# TCAN1146_PWR_MGMT.net
KiCad netlist of a schematic drawn in Altium Designer
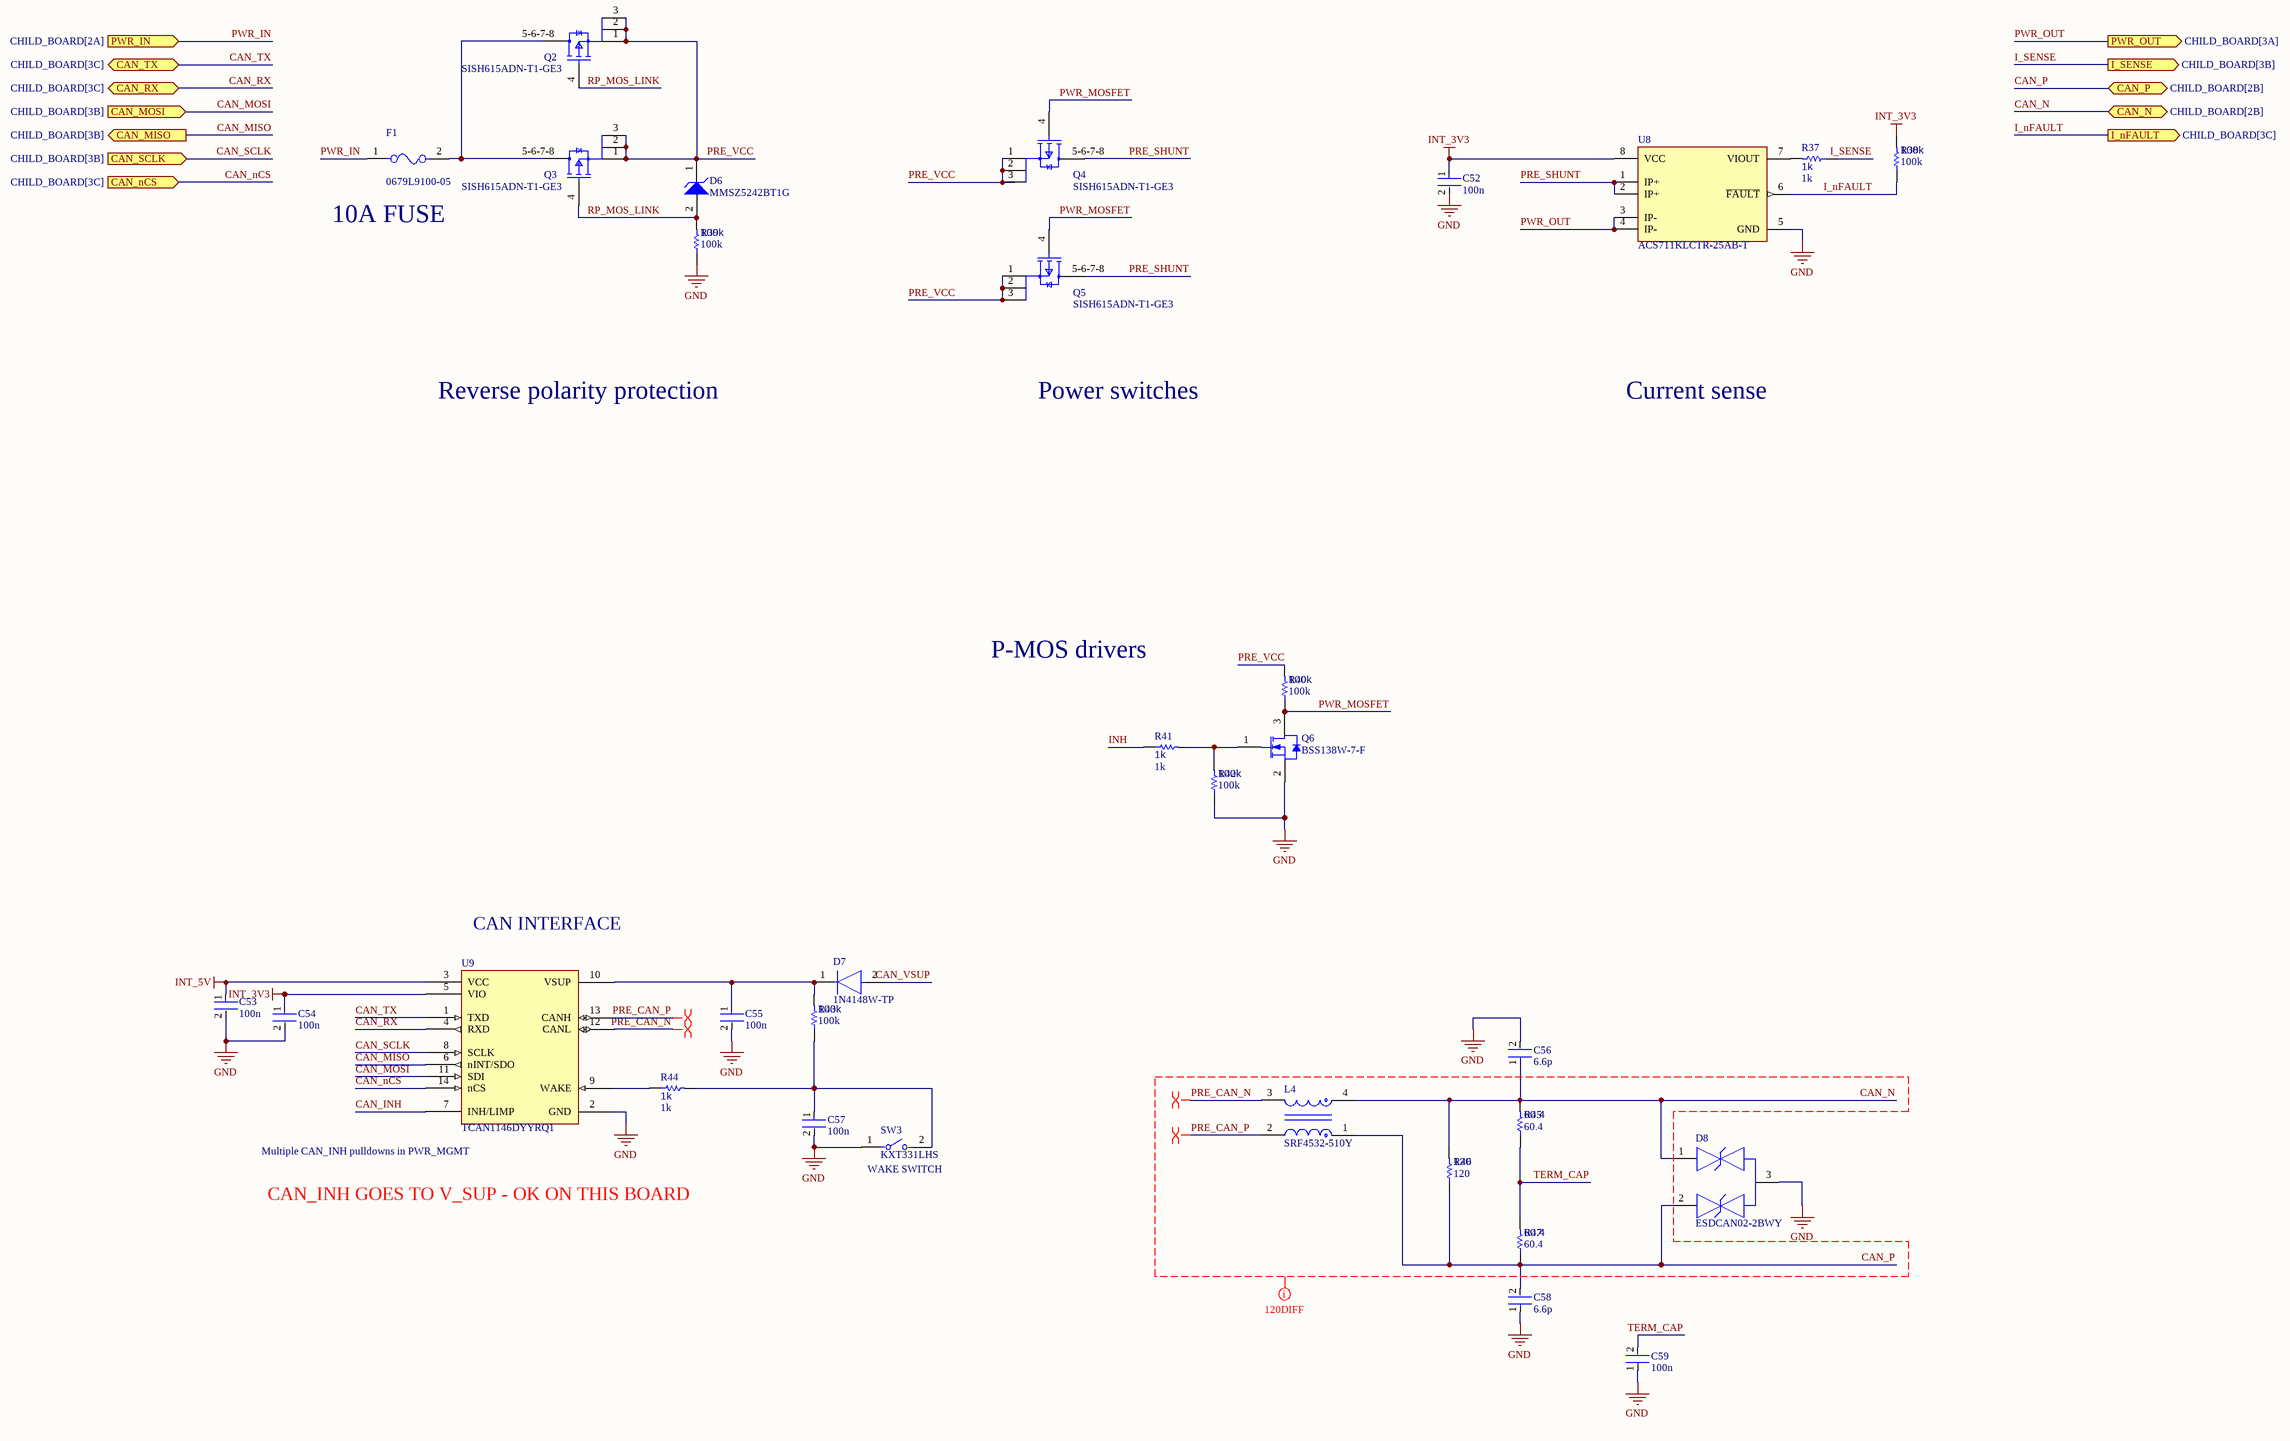
[diagram p0: TCAN1146_PWR_MGMT.SchDoc]

(export (version "E")
  (design (tool "Eeschema 10.0.6"))
  (components
    (comp (ref "C52")
      (value "100n")
      (footprint "FP-0402-L_1_0_0_05-W_0_5-IPC_A")
      (description "LARGE PADS, 0402 CAP, CHANGE COMMENT TO MATCH REAL P/N")
      (libsource (lib "Space Concordia") (part "b4654b650e69147ec39a6b967a45e02"))
    )
    (comp (ref "C53")
      (value "100n")
      (footprint "FP-0402-L_1_0_0_05-W_0_5-IPC_A")
      (description "LARGE PADS, 0402 CAP, CHANGE COMMENT TO MATCH REAL P/N")
      (libsource (lib "Space Concordia") (part "b4654b650e69147ec39a6b967a45e02"))
    )
    (comp (ref "C54")
      (value "100n")
      (footprint "FP-0402-L_1_0_0_05-W_0_5-IPC_A")
      (description "LARGE PADS, 0402 CAP, CHANGE COMMENT TO MATCH REAL P/N")
      (libsource (lib "Space Concordia") (part "b4654b650e69147ec39a6b967a45e02"))
    )
    (comp (ref "C55")
      (value "100n")
      (footprint "FP-0402-L_1_0_0_05-W_0_5-IPC_A")
      (description "LARGE PADS, 0402 CAP, CHANGE COMMENT TO MATCH REAL P/N")
      (libsource (lib "Space Concordia") (part "b4654b650e69147ec39a6b967a45e02"))
    )
    (comp (ref "C56")
      (value "6.6p")
      (footprint "FP-0402-L_1_0_0_05-W_0_5-IPC_A")
      (description "LARGE PADS, 0402 CAP, CHANGE COMMENT TO MATCH REAL P/N")
      (libsource (lib "Space Concordia") (part "b4654b650e69147ec39a6b967a45e02"))
    )
    (comp (ref "C57")
      (value "100n")
      (footprint "FP-0402-L_1_0_0_05-W_0_5-IPC_A")
      (description "LARGE PADS, 0402 CAP, CHANGE COMMENT TO MATCH REAL P/N")
      (libsource (lib "Space Concordia") (part "b4654b650e69147ec39a6b967a45e02"))
    )
    (comp (ref "C58")
      (value "6.6p")
      (footprint "FP-0402-L_1_0_0_05-W_0_5-IPC_A")
      (description "LARGE PADS, 0402 CAP, CHANGE COMMENT TO MATCH REAL P/N")
      (libsource (lib "Space Concordia") (part "b4654b650e69147ec39a6b967a45e02"))
    )
    (comp (ref "C59")
      (value "100n")
      (footprint "FP-0402-L_1_0_0_05-W_0_5-IPC_A")
      (description "LARGE PADS, 0402 CAP, CHANGE COMMENT TO MATCH REAL P/N")
      (libsource (lib "Space Concordia") (part "b4654b650e69147ec39a6b967a45e02"))
    )
    (comp (ref "D6")
      (value "MMSZ5242BT1G")
      (footprint "ONSC-SOD-123-2-425-04_V")
      (description "Zener Voltage Regulator, 500 mW, 2-Pin SOD-123, Pb-Free, Tape and Reel")
      (fields (field (name "MANUFACTURER") "On Semiconductor"))
      (libsource (lib "Altium Content Vault") (part "ONSC-K1A2-2"))
    )
    (comp (ref "D7")
      (value "1N4148W-TP")
      (footprint "FP-SOD-123-IPC_A")
      (description "DIODE GEN PURP 100V 150MA SOD123")
      (libsource (lib "Altium Content Vault") (part "d7152d700b627762746794eb795d46e"))
    )
    (comp (ref "D8")
      (value "ESDCAN02-2BWY")
      (footprint "FP-SOT323-3L-MFG")
      (description "TVS DIODE 26.5V 44V SOT323-3")
      (fields
        (field (name "MANUFACTURER") "STMicroelectronics")
        (field (name "OCTOPART") "https://octopart.com/esdcan02-2bwy-stmicroelectronics-58631133")
      )
      (libsource (lib "Altium Content Vault") (part "0b9019fb5e52ed66df21ec1535be59d"))
    )
    (comp (ref "F1")
      (value "0679L9100-05")
      (footprint "FP-0679L-MFG")
      (description "DIFF P#!!!\r\n\r\nFUSE BRD MNT 10A 125VAC/VDC")
      (fields
        (field (name "OCTOPART") "https://octopart.com/0679l9150-01-bel+fuse-70850665")
        (field (name "MANUFACTURER") "Bel Fuse")
      )
      (libsource (lib "Altium Content Vault") (part "5bcf9b9f640e542cf0359d10258e979"))
    )
    (comp (ref "L4")
      (value "SRF4532-510Y")
      (footprint "FP-SRF4532-MFG")
      (description "CMC 51UH 200MA 2LN 2KOHM SMD")
      (fields (field (name "TOLERANCE") "50%"))
      (libsource (lib "Altium Content Vault") (part "aca3f6a10b859f211cca95010157f3b"))
    )
    (comp (ref "Q2")
      (value "SISH615ADN-T1-GE3")
      (footprint "SISH615ADN-T1-GE3-Footprint-1")
      (description "Trans MOSFET P-CH 20V 22.1A 8-Pin PowerPAK 1212 EP T/R")
      (libsource (lib "Space Concordia") (part "CMP-013-00036-4"))
    )
    (comp (ref "Q3")
      (value "SISH615ADN-T1-GE3")
      (footprint "SISH615ADN-T1-GE3-Footprint-1")
      (description "Trans MOSFET P-CH 20V 22.1A 8-Pin PowerPAK 1212 EP T/R")
      (libsource (lib "Space Concordia") (part "CMP-013-00036-4"))
    )
    (comp (ref "Q4")
      (value "SISH615ADN-T1-GE3")
      (footprint "SISH615ADN-T1-GE3-Footprint-1")
      (description "Trans MOSFET P-CH 20V 22.1A 8-Pin PowerPAK 1212 EP T/R")
      (libsource (lib "Space Concordia") (part "CMP-013-00036-4"))
    )
    (comp (ref "Q5")
      (value "SISH615ADN-T1-GE3")
      (footprint "SISH615ADN-T1-GE3-Footprint-1")
      (description "Trans MOSFET P-CH 20V 22.1A 8-Pin PowerPAK 1212 EP T/R")
      (libsource (lib "Space Concordia") (part "CMP-013-00036-4"))
    )
    (comp (ref "Q6")
      (value "BSS138W-7-F")
      (footprint "DIOD-SOT323-3_V")
      (fields (field (name "MANUFACTURER") "DiodesIncorporated"))
      (libsource (lib "Altium Content Vault") (part "NEMOS-GSD-3"))
    )
    (comp (ref "R37")
      (value "1k")
      (footprint "R0603B")
      (description "Resistor")
      (fields (field (name "ALTIUM_VALUE") "1k"))
      (libsource (lib "Space Concordia") (part "Resistor"))
    )
    (comp (ref "R38")
      (value "100k")
      (footprint "R0603B")
      (description "Resistor")
      (fields (field (name "ALTIUM_VALUE") "100k"))
      (libsource (lib "Space Concordia") (part "Resistor"))
    )
    (comp (ref "R39")
      (value "100k")
      (footprint "R0603B")
      (description "Resistor")
      (fields (field (name "ALTIUM_VALUE") "100k"))
      (libsource (lib "Space Concordia") (part "Resistor"))
    )
    (comp (ref "R40")
      (value "100k")
      (footprint "R0603B")
      (description "Resistor")
      (fields (field (name "ALTIUM_VALUE") "100k"))
      (libsource (lib "Space Concordia") (part "Resistor"))
    )
    (comp (ref "R41")
      (value "1k")
      (footprint "R0603B")
      (description "Resistor")
      (fields (field (name "ALTIUM_VALUE") "1k"))
      (libsource (lib "Space Concordia") (part "Resistor"))
    )
    (comp (ref "R42")
      (value "100k")
      (footprint "R0603B")
      (description "Resistor")
      (fields (field (name "ALTIUM_VALUE") "100k"))
      (libsource (lib "Space Concordia") (part "Resistor"))
    )
    (comp (ref "R43")
      (value "100k")
      (footprint "R0603B")
      (description "Resistor")
      (fields (field (name "ALTIUM_VALUE") "100k"))
      (libsource (lib "Space Concordia") (part "Resistor"))
    )
    (comp (ref "R44")
      (value "1k")
      (footprint "R0603B")
      (description "Resistor")
      (fields (field (name "ALTIUM_VALUE") "1k"))
      (libsource (lib "Space Concordia") (part "Resistor"))
    )
    (comp (ref "R45")
      (value "60.4")
      (footprint "R0603B")
      (description "Resistor")
      (fields (field (name "ALTIUM_VALUE") "60.4"))
      (libsource (lib "Space Concordia") (part "Resistor"))
    )
    (comp (ref "R46")
      (value "120")
      (footprint "R0603B")
      (description "Resistor")
      (fields (field (name "ALTIUM_VALUE") "120"))
      (libsource (lib "Space Concordia") (part "Resistor"))
    )
    (comp (ref "R47")
      (value "60.4")
      (footprint "R0603B")
      (description "Resistor")
      (fields (field (name "ALTIUM_VALUE") "60.4"))
      (libsource (lib "Space Concordia") (part "Resistor"))
    )
    (comp (ref "SW3")
      (value "KXT331LHS")
      (footprint "FP-KXT331LHS-MFG")
      (description "SWITCH TACTILE SPST-NO 0.02A 15V")
      (libsource (lib "Altium Content Vault") (part "bb27bde45df87f1f469753f287ef5ae"))
    )
    (comp (ref "U8")
      (value "ACS711KLCTR-25AB-T")
      (footprint "FP-LC-8-IPC_A")
      (description "SENSOR CURRENT HALL 25A AC/DC")
      (libsource (lib "Altium Content Vault") (part "eeba3158841281b4ae542a6e24976ab"))
    )
    (comp (ref "U9")
      (value "TCAN1146DYYRQ1")
      (footprint "TCAN1146DYYRQ1-Footprint-1")
      (libsource (lib "Space Concordia") (part "CMP-015-00012-2"))
    )
  )
  (nets
    (net (code "1") (name "/CAN_INH") (class "Default")
      (node (ref "U9") (pin "7") (pinfunction "INH/LIMP_7") (pintype "passive"))
    )
    (net (code "2") (name "/CAN_MISO") (class "Default")
      (node (ref "U9") (pin "6") (pinfunction "nINT/SDO_6") (pintype "output"))
    )
    (net (code "3") (name "/CAN_MOSI") (class "Default")
      (node (ref "U9") (pin "11") (pinfunction "SDI_11") (pintype "input"))
    )
    (net (code "4") (name "/CAN_N") (class "Default")
      (node (ref "C56") (pin "1") (pinfunction "1_1") (pintype "passive"))
      (node (ref "D8") (pin "1") (pinfunction "1_1") (pintype "passive"))
      (node (ref "L4") (pin "4") (pinfunction "4_4") (pintype "passive"))
      (node (ref "R45") (pin "2") (pinfunction "2_2") (pintype "passive"))
      (node (ref "R46") (pin "2") (pinfunction "2_2") (pintype "passive"))
    )
    (net (code "5") (name "/CAN_P") (class "Default")
      (node (ref "C58") (pin "2") (pinfunction "2_2") (pintype "passive"))
      (node (ref "D8") (pin "2") (pinfunction "2_2") (pintype "passive"))
      (node (ref "L4") (pin "1") (pinfunction "1_1") (pintype "passive"))
      (node (ref "R46") (pin "1") (pinfunction "1_1") (pintype "passive"))
      (node (ref "R47") (pin "1") (pinfunction "1_1") (pintype "passive"))
    )
    (net (code "6") (name "/CAN_RX") (class "Default")
      (node (ref "U9") (pin "4") (pinfunction "RXD_4") (pintype "output"))
    )
    (net (code "7") (name "/CAN_SCLK") (class "Default")
      (node (ref "U9") (pin "8") (pinfunction "SCLK_8") (pintype "input"))
    )
    (net (code "8") (name "/CAN_TX") (class "Default")
      (node (ref "U9") (pin "1") (pinfunction "TXD_1") (pintype "input"))
    )
    (net (code "9") (name "/CAN_VSUP") (class "Default")
      (node (ref "D7") (pin "2") (pinfunction "A_2") (pintype "passive"))
    )
    (net (code "10") (name "/CAN_nCS") (class "Default")
      (node (ref "U9") (pin "14") (pinfunction "nCS_14") (pintype "input"))
    )
    (net (code "11") (name "/INH") (class "Default")
      (node (ref "R41") (pin "1") (pinfunction "1_1") (pintype "passive"))
    )
    (net (code "12") (name "/I_SENSE") (class "Default")
      (node (ref "R37") (pin "1") (pinfunction "1_1") (pintype "passive"))
    )
    (net (code "13") (name "/I_nFAULT") (class "Default")
      (node (ref "R38") (pin "1") (pinfunction "1_1") (pintype "passive"))
      (node (ref "U8") (pin "6") (pinfunction "~{FAULT}_6") (pintype "output"))
    )
    (net (code "14") (name "/PRE_CAN_N") (class "Default")
      (node (ref "L4") (pin "3") (pinfunction "3_3") (pintype "passive"))
      (node (ref "U9") (pin "12") (pinfunction "CANL_12") (pintype "bidirectional"))
    )
    (net (code "15") (name "/PRE_CAN_P") (class "Default")
      (node (ref "L4") (pin "2") (pinfunction "2_2") (pintype "passive"))
      (node (ref "U9") (pin "13") (pinfunction "CANH_13") (pintype "bidirectional"))
    )
    (net (code "16") (name "/PRE_SHUNT") (class "Default")
      (node (ref "Q4") (pin "5-6-7-8") (pinfunction "D_5-6-7-8") (pintype "passive"))
      (node (ref "Q5") (pin "5-6-7-8") (pinfunction "D_5-6-7-8") (pintype "passive"))
      (node (ref "U8") (pin "1") (pinfunction "IP+_1") (pintype "passive"))
      (node (ref "U8") (pin "2") (pinfunction "IP+_2") (pintype "passive"))
    )
    (net (code "17") (name "/PRE_VCC") (class "Default")
      (node (ref "D6") (pin "1") (pinfunction "K_1") (pintype "passive"))
      (node (ref "Q2") (pin "1") (pinfunction "S_1") (pintype "passive"))
      (node (ref "Q2") (pin "2") (pinfunction "S_2") (pintype "passive"))
      (node (ref "Q2") (pin "3") (pinfunction "S_3") (pintype "passive"))
      (node (ref "Q3") (pin "1") (pinfunction "S_1") (pintype "passive"))
      (node (ref "Q3") (pin "2") (pinfunction "S_2") (pintype "passive"))
      (node (ref "Q3") (pin "3") (pinfunction "S_3") (pintype "passive"))
      (node (ref "Q4") (pin "1") (pinfunction "S_1") (pintype "passive"))
      (node (ref "Q4") (pin "2") (pinfunction "S_2") (pintype "passive"))
      (node (ref "Q4") (pin "3") (pinfunction "S_3") (pintype "passive"))
      (node (ref "Q5") (pin "1") (pinfunction "S_1") (pintype "passive"))
      (node (ref "Q5") (pin "2") (pinfunction "S_2") (pintype "passive"))
      (node (ref "Q5") (pin "3") (pinfunction "S_3") (pintype "passive"))
      (node (ref "R40") (pin "2") (pinfunction "2_2") (pintype "passive"))
    )
    (net (code "18") (name "/PWR_IN") (class "Default")
      (node (ref "F1") (pin "1") (pinfunction "1_1") (pintype "passive"))
    )
    (net (code "19") (name "/PWR_MOSFET") (class "Default")
      (node (ref "Q4") (pin "4") (pinfunction "G_4") (pintype "passive"))
      (node (ref "Q5") (pin "4") (pinfunction "G_4") (pintype "passive"))
      (node (ref "Q6") (pin "3") (pinfunction "D_3") (pintype "passive"))
      (node (ref "R40") (pin "1") (pinfunction "1_1") (pintype "passive"))
    )
    (net (code "20") (name "/PWR_OUT") (class "Default")
      (node (ref "U8") (pin "3") (pinfunction "IP-_3") (pintype "passive"))
      (node (ref "U8") (pin "4") (pinfunction "IP-_4") (pintype "passive"))
    )
    (net (code "21") (name "/RP_MOS_LINK") (class "Default")
      (node (ref "D6") (pin "2") (pinfunction "A_2") (pintype "passive"))
      (node (ref "Q2") (pin "4") (pinfunction "G_4") (pintype "passive"))
      (node (ref "Q3") (pin "4") (pinfunction "G_4") (pintype "passive"))
      (node (ref "R39") (pin "2") (pinfunction "2_2") (pintype "passive"))
    )
    (net (code "22") (name "/TERM_CAP") (class "Default")
      (node (ref "C59") (pin "2") (pinfunction "2_2") (pintype "passive"))
      (node (ref "R45") (pin "1") (pinfunction "1_1") (pintype "passive"))
      (node (ref "R47") (pin "2") (pinfunction "2_2") (pintype "passive"))
    )
    (net (code "23") (name "GND") (class "Default")
      (node (ref "C52") (pin "2") (pinfunction "2_2") (pintype "passive"))
      (node (ref "C53") (pin "2") (pinfunction "2_2") (pintype "passive"))
      (node (ref "C54") (pin "2") (pinfunction "2_2") (pintype "passive"))
      (node (ref "C55") (pin "2") (pinfunction "2_2") (pintype "passive"))
      (node (ref "C56") (pin "2") (pinfunction "2_2") (pintype "passive"))
      (node (ref "C57") (pin "2") (pinfunction "2_2") (pintype "passive"))
      (node (ref "C58") (pin "1") (pinfunction "1_1") (pintype "passive"))
      (node (ref "C59") (pin "1") (pinfunction "1_1") (pintype "passive"))
      (node (ref "D8") (pin "3") (pinfunction "3_3") (pintype "passive"))
      (node (ref "Q6") (pin "2") (pinfunction "S_2") (pintype "passive"))
      (node (ref "R39") (pin "1") (pinfunction "1_1") (pintype "passive"))
      (node (ref "R42") (pin "1") (pinfunction "1_1") (pintype "passive"))
      (node (ref "SW3") (pin "1") (pinfunction "1_1") (pintype "passive"))
      (node (ref "U8") (pin "5") (pinfunction "GND_5") (pintype "power_in"))
      (node (ref "U9") (pin "2") (pinfunction "GND_2") (pintype "power_in"))
    )
    (net (code "24") (name "INT_3V3") (class "Default")
      (node (ref "C52") (pin "1") (pinfunction "1_1") (pintype "passive"))
      (node (ref "C54") (pin "1") (pinfunction "1_1") (pintype "passive"))
      (node (ref "R38") (pin "2") (pinfunction "2_2") (pintype "passive"))
      (node (ref "U8") (pin "8") (pinfunction "VCC_8") (pintype "power_in"))
      (node (ref "U9") (pin "5") (pinfunction "VIO_5") (pintype "power_in"))
    )
    (net (code "25") (name "INT_5V") (class "Default")
      (node (ref "C53") (pin "1") (pinfunction "1_1") (pintype "passive"))
      (node (ref "U9") (pin "3") (pinfunction "VCC_3") (pintype "power_in"))
    )
    (net (code "26") (name "Net-(C57-Pad1)") (class "Default")
      (node (ref "C57") (pin "1") (pinfunction "1_1") (pintype "passive"))
      (node (ref "R43") (pin "1") (pinfunction "1_1") (pintype "passive"))
      (node (ref "R44") (pin "2") (pinfunction "2_2") (pintype "passive"))
      (node (ref "SW3") (pin "2") (pinfunction "2_2") (pintype "passive"))
    )
    (net (code "27") (name "Net-(D7-C)") (class "Default")
      (node (ref "C55") (pin "1") (pinfunction "1_1") (pintype "passive"))
      (node (ref "D7") (pin "1") (pinfunction "C_1") (pintype "passive"))
      (node (ref "R43") (pin "2") (pinfunction "2_2") (pintype "passive"))
      (node (ref "U9") (pin "10") (pinfunction "VSUP_10") (pintype "power_in"))
    )
    (net (code "28") (name "Net-(Q2-D)") (class "Default")
      (node (ref "F1") (pin "2") (pinfunction "2_2") (pintype "passive"))
      (node (ref "Q2") (pin "5-6-7-8") (pinfunction "D_5-6-7-8") (pintype "passive"))
      (node (ref "Q3") (pin "5-6-7-8") (pinfunction "D_5-6-7-8") (pintype "passive"))
    )
    (net (code "29") (name "Net-(Q6-G)") (class "Default")
      (node (ref "Q6") (pin "1") (pinfunction "G_1") (pintype "passive"))
      (node (ref "R41") (pin "2") (pinfunction "2_2") (pintype "passive"))
      (node (ref "R42") (pin "2") (pinfunction "2_2") (pintype "passive"))
    )
    (net (code "30") (name "Net-(U8-VIOUT)") (class "Default")
      (node (ref "R37") (pin "2") (pinfunction "2_2") (pintype "passive"))
      (node (ref "U8") (pin "7") (pinfunction "VIOUT_7") (pintype "passive"))
    )
    (net (code "31") (name "Net-(U9-WAKE)") (class "Default")
      (node (ref "R44") (pin "1") (pinfunction "1_1") (pintype "passive"))
      (node (ref "U9") (pin "9") (pinfunction "WAKE_9") (pintype "input"))
    )
  )
)
